# op_amp_with_single_power.net
KiCad netlist of a schematic drawn in Altium Designer
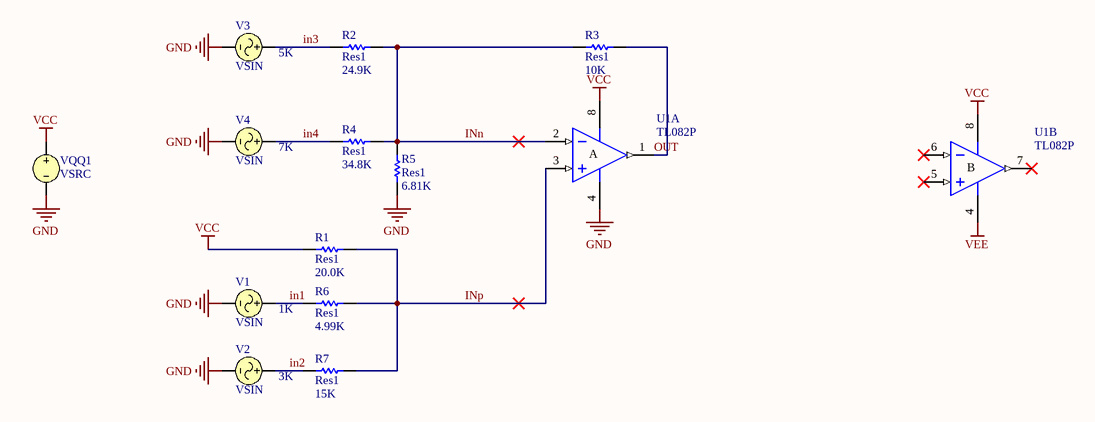
[diagram p0: op_amp_with_single_power.SchDoc]

(export (version "E")
  (design (tool "Eeschema 10.0.6"))
  (components
    (comp (ref "R1")
      (value "Res1")
      (footprint "AXIAL-0.3")
      (description "Resistor")
      (fields (field (name "ALTIUM_VALUE") "20.0K") (field (name "PUBLISHER") "Altium Limited"))
      (libsource (lib "Miscellaneous Devices") (part "Res1"))
    )
    (comp (ref "R2")
      (value "Res1")
      (footprint "AXIAL-0.3")
      (description "Resistor")
      (fields (field (name "ALTIUM_VALUE") "24.9K") (field (name "PUBLISHER") "Altium Limited"))
      (libsource (lib "Miscellaneous Devices") (part "Res1"))
    )
    (comp (ref "R3")
      (value "Res1")
      (footprint "AXIAL-0.3")
      (description "Resistor")
      (fields (field (name "ALTIUM_VALUE") "10K") (field (name "PUBLISHER") "Altium Limited"))
      (libsource (lib "Miscellaneous Devices") (part "Res1"))
    )
    (comp (ref "R4")
      (value "Res1")
      (footprint "AXIAL-0.3")
      (description "Resistor")
      (fields (field (name "ALTIUM_VALUE") "34.8K") (field (name "PUBLISHER") "Altium Limited"))
      (libsource (lib "Miscellaneous Devices") (part "Res1"))
    )
    (comp (ref "R5")
      (value "Res1")
      (footprint "AXIAL-0.3")
      (description "Resistor")
      (fields (field (name "ALTIUM_VALUE") "6.81K") (field (name "PUBLISHER") "Altium Limited"))
      (libsource (lib "Miscellaneous Devices") (part "Res1"))
    )
    (comp (ref "R6")
      (value "Res1")
      (footprint "AXIAL-0.3")
      (description "Resistor")
      (fields (field (name "ALTIUM_VALUE") "4.99K") (field (name "PUBLISHER") "Altium Limited"))
      (libsource (lib "Miscellaneous Devices") (part "Res1"))
    )
    (comp (ref "R7")
      (value "Res1")
      (footprint "AXIAL-0.3")
      (description "Resistor")
      (fields (field (name "ALTIUM_VALUE") "15K") (field (name "PUBLISHER") "Altium Limited"))
      (libsource (lib "Miscellaneous Devices") (part "Res1"))
    )
    (comp (ref "U1")
      (value "TL082P")
      (footprint "P008")
      (description "JFET-Input Operational Amplifier")
      (fields (field (name "PUBLISHER") "Altium Limited"))
      (libsource (lib "TI Operational Amplifier") (part "TL082P"))
    )
    (comp (ref "V1")
      (value "VSIN")
      (description "Sinusoidal Voltage Source")
      (fields (field (name "FREQUENCY") "1K") (field (name "PUBLISHER") "Altium Limited"))
      (libsource (lib "Simulation Sources") (part "VSIN"))
    )
    (comp (ref "V2")
      (value "VSIN")
      (description "Sinusoidal Voltage Source")
      (fields (field (name "FREQUENCY") "3K") (field (name "PUBLISHER") "Altium Limited"))
      (libsource (lib "Simulation Sources") (part "VSIN"))
    )
    (comp (ref "V3")
      (value "VSIN")
      (description "Sinusoidal Voltage Source")
      (fields (field (name "FREQUENCY") "5K") (field (name "PUBLISHER") "Altium Limited"))
      (libsource (lib "Simulation Sources") (part "VSIN"))
    )
    (comp (ref "V4")
      (value "VSIN")
      (description "Sinusoidal Voltage Source")
      (fields (field (name "FREQUENCY") "7K") (field (name "PUBLISHER") "Altium Limited"))
      (libsource (lib "Simulation Sources") (part "VSIN"))
    )
    (comp (ref "VQQ1")
      (value "VSRC")
      (description "Voltage Source")
      (fields (field (name "PUBLISHER") "Altium Limited"))
      (libsource (lib "Simulation Sources") (part "VSRC"))
    )
  )
  (nets
    (net (code "1") (name "/INn") (class "Default")
      (node (ref "R2") (pin "2") (pinfunction "2_2") (pintype "passive"))
      (node (ref "R3") (pin "1") (pinfunction "1_1") (pintype "passive"))
      (node (ref "R4") (pin "2") (pinfunction "2_2") (pintype "passive"))
      (node (ref "R5") (pin "2") (pinfunction "2_2") (pintype "passive"))
      (node (ref "U1") (pin "2") (pinfunction "IN-_2") (pintype "input"))
    )
    (net (code "2") (name "/INp") (class "Default")
      (node (ref "R1") (pin "1") (pinfunction "1_1") (pintype "passive"))
      (node (ref "R6") (pin "2") (pinfunction "2_2") (pintype "passive"))
      (node (ref "R7") (pin "2") (pinfunction "2_2") (pintype "passive"))
      (node (ref "U1") (pin "3") (pinfunction "IN+_3") (pintype "input"))
    )
    (net (code "3") (name "/OUT") (class "Default")
      (node (ref "R3") (pin "2") (pinfunction "2_2") (pintype "passive"))
      (node (ref "U1") (pin "1") (pinfunction "OUT_1") (pintype "output"))
    )
    (net (code "4") (name "/in1") (class "Default")
      (node (ref "R6") (pin "1") (pinfunction "1_1") (pintype "passive"))
      (node (ref "V1") (pin "1") (pinfunction "1_1") (pintype "passive"))
    )
    (net (code "5") (name "/in2") (class "Default")
      (node (ref "R7") (pin "1") (pinfunction "1_1") (pintype "passive"))
      (node (ref "V2") (pin "1") (pinfunction "1_1") (pintype "passive"))
    )
    (net (code "6") (name "/in3") (class "Default")
      (node (ref "R2") (pin "1") (pinfunction "1_1") (pintype "passive"))
      (node (ref "V3") (pin "1") (pinfunction "1_1") (pintype "passive"))
    )
    (net (code "7") (name "/in4") (class "Default")
      (node (ref "R4") (pin "1") (pinfunction "1_1") (pintype "passive"))
      (node (ref "V4") (pin "1") (pinfunction "1_1") (pintype "passive"))
    )
    (net (code "8") (name "GND") (class "Default")
      (node (ref "R5") (pin "1") (pinfunction "1_1") (pintype "passive"))
      (node (ref "U1") (pin "4") (pinfunction "V-_4") (pintype "power_in"))
      (node (ref "V1") (pin "2") (pinfunction "2_2") (pintype "passive"))
      (node (ref "V2") (pin "2") (pinfunction "2_2") (pintype "passive"))
      (node (ref "V3") (pin "2") (pinfunction "2_2") (pintype "passive"))
      (node (ref "V4") (pin "2") (pinfunction "2_2") (pintype "passive"))
      (node (ref "VQQ1") (pin "2") (pinfunction "2_2") (pintype "passive"))
    )
    (net (code "9") (name "VCC") (class "Default")
      (node (ref "R1") (pin "2") (pinfunction "2_2") (pintype "passive"))
      (node (ref "U1") (pin "8") (pinfunction "V+_8") (pintype "power_in"))
      (node (ref "VQQ1") (pin "1") (pinfunction "1_1") (pintype "passive"))
    )
    (net (code "10") (name "VEE") (class "Default")
      (node (ref "U1") (pin "4") (pinfunction "V-_4") (pintype "power_in"))
    )
    (net (code "11") (name "unconnected-(U1B-IN+-Pad5)") (class "Default")
      (node (ref "U1") (pin "5") (pinfunction "IN+_5") (pintype "input+no_connect"))
    )
    (net (code "12") (name "unconnected-(U1B-IN--Pad6)") (class "Default")
      (node (ref "U1") (pin "6") (pinfunction "IN-_6") (pintype "input+no_connect"))
    )
    (net (code "13") (name "unconnected-(U1B-OUT-Pad7)") (class "Default")
      (node (ref "U1") (pin "7") (pinfunction "OUT_7") (pintype "output+no_connect"))
    )
  )
)
